# ppc_extbus.net
KiCad netlist of a schematic drawn in Altium Designer
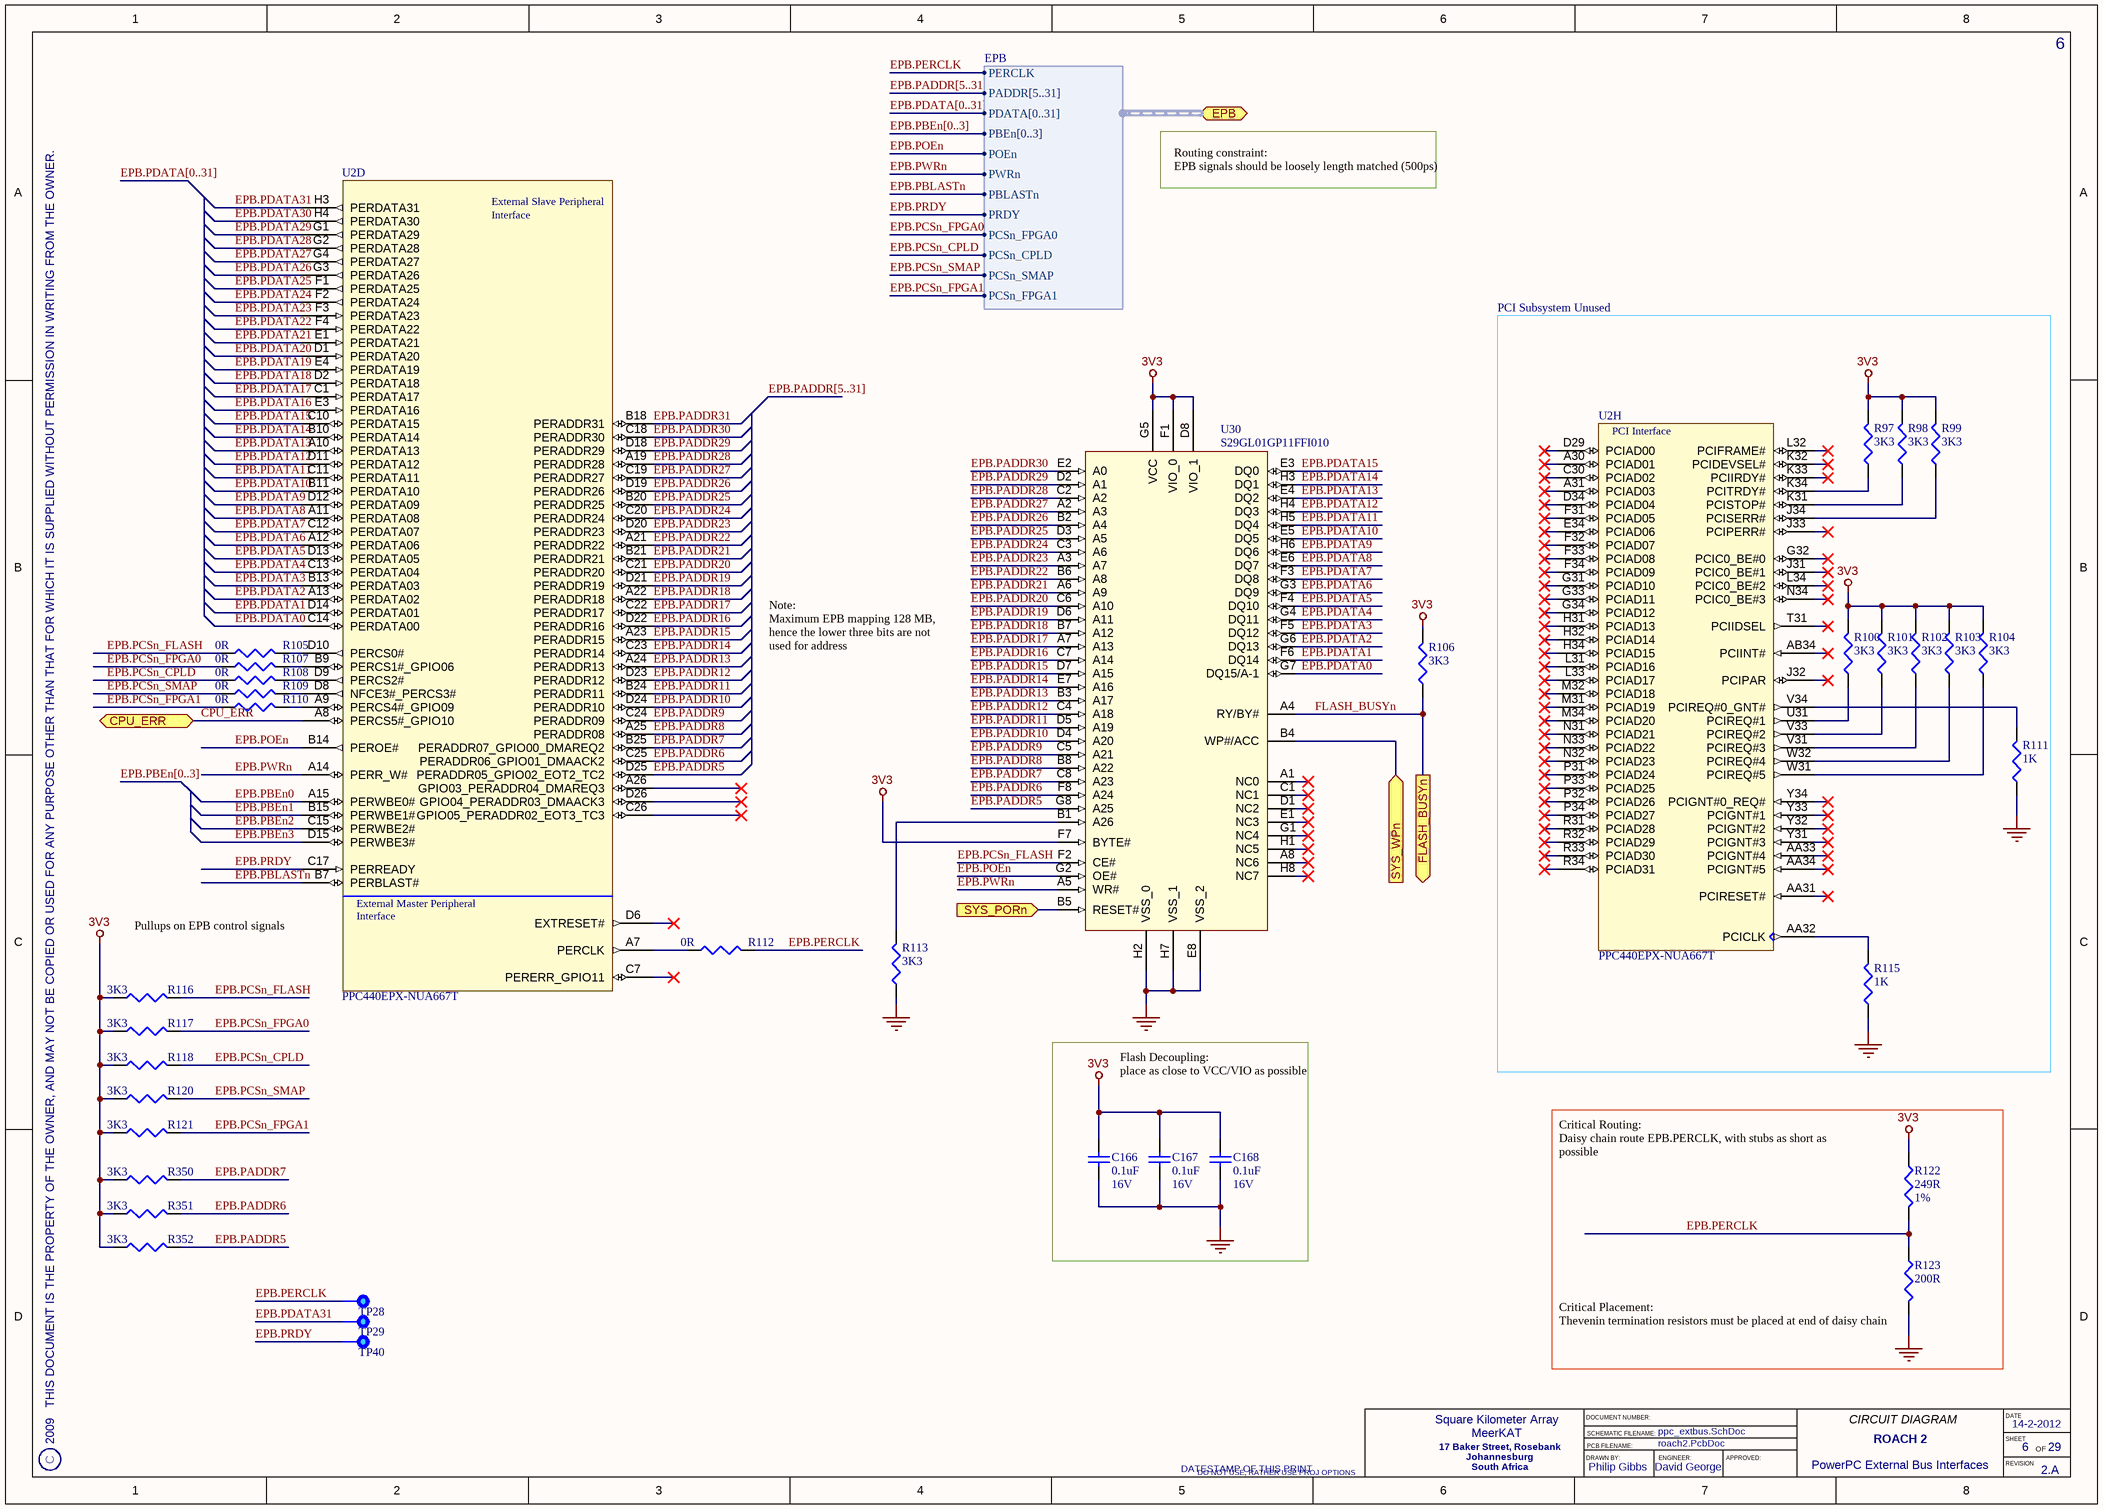
[diagram p0: ppc_extbus.SchDoc]

(export (version "E")
  (design (tool "Eeschema 10.0.6"))
  (components
    (comp (ref "C166")
      (value "0.1uF")
      (footprint "CAPC1005X60L")
      (description "0.1uF, Ceramic Capacitor")
      (fields
        (field (name "MANUFACTURER") "VENKEL")
        (field (name "PARTNUM") "C0402X7R160-104KN")
        (field (name "RATING") "16V")
      )
      (libsource (lib "altium_db") (part "CapStd"))
    )
    (comp (ref "C167")
      (value "0.1uF")
      (footprint "CAPC1005X60L")
      (description "0.1uF, Ceramic Capacitor")
      (fields
        (field (name "MANUFACTURER") "VENKEL")
        (field (name "PARTNUM") "C0402X7R160-104KN")
        (field (name "RATING") "16V")
      )
      (libsource (lib "altium_db") (part "CapStd"))
    )
    (comp (ref "C168")
      (value "0.1uF")
      (footprint "CAPC1005X60L")
      (description "0.1uF, Ceramic Capacitor")
      (fields
        (field (name "MANUFACTURER") "VENKEL")
        (field (name "PARTNUM") "C0402X7R160-104KN")
        (field (name "RATING") "16V")
      )
      (libsource (lib "altium_db") (part "CapStd"))
    )
    (comp (ref "R97")
      (value "3K3")
      (footprint "RESC1005X40L")
      (description "3K3, 1.1mm x 0.5mm, Thick Film Resistor")
      (fields (field (name "MANUFACTURER") "ROYALOHM") (field (name "PARTNUM") "0402WGJ0332T1E"))
      (libsource (lib "altium_db") (part "ResStd"))
    )
    (comp (ref "R98")
      (value "3K3")
      (footprint "RESC1005X40L")
      (description "3K3, 1.1mm x 0.5mm, Thick Film Resistor")
      (fields (field (name "MANUFACTURER") "ROYALOHM") (field (name "PARTNUM") "0402WGJ0332T1E"))
      (libsource (lib "altium_db") (part "ResStd"))
    )
    (comp (ref "R99")
      (value "3K3")
      (footprint "RESC1005X40L")
      (description "3K3, 1.1mm x 0.5mm, Thick Film Resistor")
      (fields (field (name "MANUFACTURER") "ROYALOHM") (field (name "PARTNUM") "0402WGJ0332T1E"))
      (libsource (lib "altium_db") (part "ResStd"))
    )
    (comp (ref "R100")
      (value "3K3")
      (footprint "RESC1005X40L")
      (description "3K3, 1.1mm x 0.5mm, Thick Film Resistor")
      (fields (field (name "MANUFACTURER") "ROYALOHM") (field (name "PARTNUM") "0402WGJ0332T1E"))
      (libsource (lib "altium_db") (part "ResStd"))
    )
    (comp (ref "R101")
      (value "3K3")
      (footprint "RESC1005X40L")
      (description "3K3, 1.1mm x 0.5mm, Thick Film Resistor")
      (fields (field (name "MANUFACTURER") "ROYALOHM") (field (name "PARTNUM") "0402WGJ0332T1E"))
      (libsource (lib "altium_db") (part "ResStd"))
    )
    (comp (ref "R102")
      (value "3K3")
      (footprint "RESC1005X40L")
      (description "3K3, 1.1mm x 0.5mm, Thick Film Resistor")
      (fields (field (name "MANUFACTURER") "ROYALOHM") (field (name "PARTNUM") "0402WGJ0332T1E"))
      (libsource (lib "altium_db") (part "ResStd"))
    )
    (comp (ref "R103")
      (value "3K3")
      (footprint "RESC1005X40L")
      (description "3K3, 1.1mm x 0.5mm, Thick Film Resistor")
      (fields (field (name "MANUFACTURER") "ROYALOHM") (field (name "PARTNUM") "0402WGJ0332T1E"))
      (libsource (lib "altium_db") (part "ResStd"))
    )
    (comp (ref "R104")
      (value "3K3")
      (footprint "RESC1005X40L")
      (description "3K3, 1.1mm x 0.5mm, Thick Film Resistor")
      (fields (field (name "MANUFACTURER") "ROYALOHM") (field (name "PARTNUM") "0402WGJ0332T1E"))
      (libsource (lib "altium_db") (part "ResStd"))
    )
    (comp (ref "R105")
      (value "0R")
      (footprint "RESC1005X40L")
      (description "0R, 1.1mm x 0.5mm, Thick Film Resistor")
      (fields (field (name "MANUFACTURER") "ROYALOHM") (field (name "PARTNUM") "0402WG00000T1E"))
      (libsource (lib "altium_db") (part "ResStd"))
    )
    (comp (ref "R106")
      (value "3K3")
      (footprint "RESC1005X40L")
      (description "3K3, 1.1mm x 0.5mm, Thick Film Resistor")
      (fields (field (name "MANUFACTURER") "ROYALOHM") (field (name "PARTNUM") "0402WGJ0332T1E"))
      (libsource (lib "altium_db") (part "ResStd"))
    )
    (comp (ref "R107")
      (value "0R")
      (footprint "RESC1005X40L")
      (description "0R, 1.1mm x 0.5mm, Thick Film Resistor")
      (fields (field (name "MANUFACTURER") "ROYALOHM") (field (name "PARTNUM") "0402WG00000T1E"))
      (libsource (lib "altium_db") (part "ResStd"))
    )
    (comp (ref "R108")
      (value "0R")
      (footprint "RESC1005X40L")
      (description "0R, 1.1mm x 0.5mm, Thick Film Resistor")
      (fields (field (name "MANUFACTURER") "ROYALOHM") (field (name "PARTNUM") "0402WG00000T1E"))
      (libsource (lib "altium_db") (part "ResStd"))
    )
    (comp (ref "R109")
      (value "0R")
      (footprint "RESC1005X40L")
      (description "0R, 1.1mm x 0.5mm, Thick Film Resistor")
      (fields (field (name "MANUFACTURER") "ROYALOHM") (field (name "PARTNUM") "0402WG00000T1E"))
      (libsource (lib "altium_db") (part "ResStd"))
    )
    (comp (ref "R110")
      (value "0R")
      (footprint "RESC1005X40L")
      (description "0R, 1.1mm x 0.5mm, Thick Film Resistor")
      (fields (field (name "MANUFACTURER") "ROYALOHM") (field (name "PARTNUM") "0402WG00000T1E"))
      (libsource (lib "altium_db") (part "ResStd"))
    )
    (comp (ref "R111")
      (value "1K")
      (footprint "RESC1005X40L")
      (description "1K, 1.1mm x 0.5mm, Thick Film Resistor")
      (fields (field (name "MANUFACTURER") "ROYALOHM") (field (name "PARTNUM") "0402WGJ0102T1E"))
      (libsource (lib "altium_db") (part "ResStd"))
    )
    (comp (ref "R112")
      (value "0R")
      (footprint "RESC1005X40L")
      (description "0R, 1.1mm x 0.5mm, Thick Film Resistor")
      (fields (field (name "MANUFACTURER") "ROYALOHM") (field (name "PARTNUM") "0402WG00000T1E"))
      (libsource (lib "altium_db") (part "ResStd"))
    )
    (comp (ref "R113")
      (value "3K3")
      (footprint "RESC1005X40L")
      (description "3K3, 1.1mm x 0.5mm, Thick Film Resistor")
      (fields (field (name "MANUFACTURER") "ROYALOHM") (field (name "PARTNUM") "0402WGJ0332T1E"))
      (libsource (lib "altium_db") (part "ResStd"))
    )
    (comp (ref "R115")
      (value "1K")
      (footprint "RESC1005X40L")
      (description "1K, 1.1mm x 0.5mm, Thick Film Resistor")
      (fields (field (name "MANUFACTURER") "ROYALOHM") (field (name "PARTNUM") "0402WGJ0102T1E"))
      (libsource (lib "altium_db") (part "ResStd"))
    )
    (comp (ref "R116")
      (value "3K3")
      (footprint "RESC1005X40L")
      (description "3K3, 1.1mm x 0.5mm, Thick Film Resistor")
      (fields (field (name "MANUFACTURER") "ROYALOHM") (field (name "PARTNUM") "0402WGJ0332T1E"))
      (libsource (lib "altium_db") (part "ResStd"))
    )
    (comp (ref "R117")
      (value "3K3")
      (footprint "RESC1005X40L")
      (description "3K3, 1.1mm x 0.5mm, Thick Film Resistor")
      (fields (field (name "MANUFACTURER") "ROYALOHM") (field (name "PARTNUM") "0402WGJ0332T1E"))
      (libsource (lib "altium_db") (part "ResStd"))
    )
    (comp (ref "R118")
      (value "3K3")
      (footprint "RESC1005X40L")
      (description "3K3, 1.1mm x 0.5mm, Thick Film Resistor")
      (fields (field (name "MANUFACTURER") "ROYALOHM") (field (name "PARTNUM") "0402WGJ0332T1E"))
      (libsource (lib "altium_db") (part "ResStd"))
    )
    (comp (ref "R120")
      (value "3K3")
      (footprint "RESC1005X40L")
      (description "3K3, 1.1mm x 0.5mm, Thick Film Resistor")
      (fields (field (name "MANUFACTURER") "ROYALOHM") (field (name "PARTNUM") "0402WGJ0332T1E"))
      (libsource (lib "altium_db") (part "ResStd"))
    )
    (comp (ref "R121")
      (value "3K3")
      (footprint "RESC1005X40L")
      (description "3K3, 1.1mm x 0.5mm, Thick Film Resistor")
      (fields (field (name "MANUFACTURER") "ROYALOHM") (field (name "PARTNUM") "0402WGJ0332T1E"))
      (libsource (lib "altium_db") (part "ResStd"))
    )
    (comp (ref "R122")
      (value "249R")
      (footprint "RESC1005X40L")
      (description "249R, 1.1mm x 0.5mm, Thick Film Resistor")
      (fields
        (field (name "MANUFACTURER") "ROYALOHM")
        (field (name "PARTNUM") "0402WGF2490T1E")
        (field (name "TOLERANCE") "1%")
      )
      (libsource (lib "altium_db") (part "ResStd"))
    )
    (comp (ref "R123")
      (value "200R")
      (footprint "RESC1005X40L")
      (description "200R, 1.1mm x 0.5mm, Thick Film Resistor")
      (fields (field (name "MANUFACTURER") "ROYALOHM") (field (name "PARTNUM") "0402WGF0201T1E"))
      (libsource (lib "altium_db") (part "ResStd"))
    )
    (comp (ref "R350")
      (value "3K3")
      (footprint "RESC1005X40L")
      (description "3K3, 1.1mm x 0.5mm, Thick Film Resistor")
      (fields (field (name "MANUFACTURER") "ROYALOHM") (field (name "PARTNUM") "0402WGJ0332T1E"))
      (libsource (lib "altium_db") (part "ResStd"))
    )
    (comp (ref "R351")
      (value "3K3")
      (footprint "RESC1005X40L")
      (description "3K3, 1.1mm x 0.5mm, Thick Film Resistor")
      (fields (field (name "MANUFACTURER") "ROYALOHM") (field (name "PARTNUM") "0402WGJ0332T1E"))
      (libsource (lib "altium_db") (part "ResStd"))
    )
    (comp (ref "R352")
      (value "3K3")
      (footprint "RESC1005X40L")
      (description "3K3, 1.1mm x 0.5mm, Thick Film Resistor")
      (fields (field (name "MANUFACTURER") "ROYALOHM") (field (name "PARTNUM") "0402WGJ0332T1E"))
      (libsource (lib "altium_db") (part "ResStd"))
    )
    (comp (ref "TP28")
      (value "Testpoint")
      (footprint "TP100")
      (description "1mm Diameter, through-hole, Circular Test-point")
      (libsource (lib "altium_db") (part "Testpoint"))
    )
    (comp (ref "TP29")
      (value "Testpoint")
      (footprint "TP100")
      (description "1mm Diameter, through-hole, Circular Test-point")
      (libsource (lib "altium_db") (part "Testpoint"))
    )
    (comp (ref "TP40")
      (value "Testpoint")
      (footprint "TP100")
      (description "1mm Diameter, through-hole, Circular Test-point")
      (libsource (lib "altium_db") (part "Testpoint"))
    )
    (comp (ref "U2")
      (value "PPC440EPX-NUA667T")
      (footprint "TE-PBGA680")
      (description "667MHz, non-RoHS, PPC440EPx uProcessor")
      (fields (field (name "MANUFACTURER") "Applied Micro"))
      (libsource (lib "altium_db") (part "PPC440EPX"))
    )
    (comp (ref "U30")
      (value "S29GL01GP11FFI010")
      (footprint "LAA064")
      (description "3V, 1 Gigabit NOR Flash")
      (fields (field (name "MANUFACTURER") "Spansion"))
      (libsource (lib "altium_db") (part "S29GL01GP"))
    )
  )
  (nets
    (net (code "2") (name "/CPU_ERR") (class "Default")
      (node (ref "U2") (pin "A8") (pinfunction "PERCS5#_GPIO10_A8") (pintype "bidirectional"))
    )
    (net (code "3") (name "/EPB.PADDR5") (class "Default")
      (node (ref "R352") (pin "2") (pinfunction "2_2") (pintype "passive"))
      (node (ref "U2") (pin "D25") (pinfunction "PERADDR05_GPIO02_EOT2_TC2_D25") (pintype "bidirectional"))
      (node (ref "U30") (pin "G8") (pinfunction "A25_G8") (pintype "input"))
    )
    (net (code "4") (name "/EPB.PADDR6") (class "Default")
      (node (ref "R351") (pin "2") (pinfunction "2_2") (pintype "passive"))
      (node (ref "U2") (pin "C25") (pinfunction "PERADDR06_GPIO01_DMAACK2_C25") (pintype "bidirectional"))
      (node (ref "U30") (pin "F8") (pinfunction "A24_F8") (pintype "input"))
    )
    (net (code "5") (name "/EPB.PADDR7") (class "Default")
      (node (ref "R350") (pin "2") (pinfunction "2_2") (pintype "passive"))
      (node (ref "U2") (pin "B25") (pinfunction "PERADDR07_GPIO00_DMAREQ2_B25") (pintype "bidirectional"))
      (node (ref "U30") (pin "C8") (pinfunction "A23_C8") (pintype "input"))
    )
    (net (code "6") (name "/EPB.PADDR8") (class "Default")
      (node (ref "U2") (pin "A25") (pinfunction "PERADDR08_A25") (pintype "bidirectional"))
      (node (ref "U30") (pin "B8") (pinfunction "A22_B8") (pintype "input"))
    )
    (net (code "7") (name "/EPB.PADDR9") (class "Default")
      (node (ref "U2") (pin "C24") (pinfunction "PERADDR09_C24") (pintype "bidirectional"))
      (node (ref "U30") (pin "C5") (pinfunction "A21_C5") (pintype "input"))
    )
    (net (code "8") (name "/EPB.PADDR10") (class "Default")
      (node (ref "U2") (pin "D24") (pinfunction "PERADDR10_D24") (pintype "bidirectional"))
      (node (ref "U30") (pin "D4") (pinfunction "A20_D4") (pintype "input"))
    )
    (net (code "9") (name "/EPB.PADDR11") (class "Default")
      (node (ref "U2") (pin "B24") (pinfunction "PERADDR11_B24") (pintype "bidirectional"))
      (node (ref "U30") (pin "D5") (pinfunction "A19_D5") (pintype "input"))
    )
    (net (code "10") (name "/EPB.PADDR12") (class "Default")
      (node (ref "U2") (pin "D23") (pinfunction "PERADDR12_D23") (pintype "bidirectional"))
      (node (ref "U30") (pin "C4") (pinfunction "A18_C4") (pintype "input"))
    )
    (net (code "11") (name "/EPB.PADDR13") (class "Default")
      (node (ref "U2") (pin "A24") (pinfunction "PERADDR13_A24") (pintype "bidirectional"))
      (node (ref "U30") (pin "B3") (pinfunction "A17_B3") (pintype "input"))
    )
    (net (code "12") (name "/EPB.PADDR14") (class "Default")
      (node (ref "U2") (pin "C23") (pinfunction "PERADDR14_C23") (pintype "bidirectional"))
      (node (ref "U30") (pin "E7") (pinfunction "A16_E7") (pintype "input"))
    )
    (net (code "13") (name "/EPB.PADDR15") (class "Default")
      (node (ref "U2") (pin "A23") (pinfunction "PERADDR15_A23") (pintype "bidirectional"))
      (node (ref "U30") (pin "D7") (pinfunction "A15_D7") (pintype "input"))
    )
    (net (code "14") (name "/EPB.PADDR16") (class "Default")
      (node (ref "U2") (pin "D22") (pinfunction "PERADDR16_D22") (pintype "bidirectional"))
      (node (ref "U30") (pin "C7") (pinfunction "A14_C7") (pintype "input"))
    )
    (net (code "15") (name "/EPB.PADDR17") (class "Default")
      (node (ref "U2") (pin "C22") (pinfunction "PERADDR17_C22") (pintype "bidirectional"))
      (node (ref "U30") (pin "A7") (pinfunction "A13_A7") (pintype "input"))
    )
    (net (code "16") (name "/EPB.PADDR18") (class "Default")
      (node (ref "U2") (pin "A22") (pinfunction "PERADDR18_A22") (pintype "bidirectional"))
      (node (ref "U30") (pin "B7") (pinfunction "A12_B7") (pintype "input"))
    )
    (net (code "17") (name "/EPB.PADDR19") (class "Default")
      (node (ref "U2") (pin "D21") (pinfunction "PERADDR19_D21") (pintype "bidirectional"))
      (node (ref "U30") (pin "D6") (pinfunction "A11_D6") (pintype "input"))
    )
    (net (code "18") (name "/EPB.PADDR20") (class "Default")
      (node (ref "U2") (pin "C21") (pinfunction "PERADDR20_C21") (pintype "bidirectional"))
      (node (ref "U30") (pin "C6") (pinfunction "A10_C6") (pintype "input"))
    )
    (net (code "19") (name "/EPB.PADDR21") (class "Default")
      (node (ref "U2") (pin "B21") (pinfunction "PERADDR21_B21") (pintype "bidirectional"))
      (node (ref "U30") (pin "A6") (pinfunction "A9_A6") (pintype "input"))
    )
    (net (code "20") (name "/EPB.PADDR22") (class "Default")
      (node (ref "U2") (pin "A21") (pinfunction "PERADDR22_A21") (pintype "bidirectional"))
      (node (ref "U30") (pin "B6") (pinfunction "A8_B6") (pintype "input"))
    )
    (net (code "21") (name "/EPB.PADDR23") (class "Default")
      (node (ref "U2") (pin "D20") (pinfunction "PERADDR23_D20") (pintype "bidirectional"))
      (node (ref "U30") (pin "A3") (pinfunction "A7_A3") (pintype "input"))
    )
    (net (code "22") (name "/EPB.PADDR24") (class "Default")
      (node (ref "U2") (pin "C20") (pinfunction "PERADDR24_C20") (pintype "bidirectional"))
      (node (ref "U30") (pin "C3") (pinfunction "A6_C3") (pintype "input"))
    )
    (net (code "23") (name "/EPB.PADDR25") (class "Default")
      (node (ref "U2") (pin "B20") (pinfunction "PERADDR25_B20") (pintype "bidirectional"))
      (node (ref "U30") (pin "D3") (pinfunction "A5_D3") (pintype "input"))
    )
    (net (code "24") (name "/EPB.PADDR26") (class "Default")
      (node (ref "U2") (pin "D19") (pinfunction "PERADDR26_D19") (pintype "bidirectional"))
      (node (ref "U30") (pin "B2") (pinfunction "A4_B2") (pintype "input"))
    )
    (net (code "25") (name "/EPB.PADDR27") (class "Default")
      (node (ref "U2") (pin "C19") (pinfunction "PERADDR27_C19") (pintype "bidirectional"))
      (node (ref "U30") (pin "A2") (pinfunction "A3_A2") (pintype "input"))
    )
    (net (code "26") (name "/EPB.PADDR28") (class "Default")
      (node (ref "U2") (pin "A19") (pinfunction "PERADDR28_A19") (pintype "bidirectional"))
      (node (ref "U30") (pin "C2") (pinfunction "A2_C2") (pintype "input"))
    )
    (net (code "27") (name "/EPB.PADDR29") (class "Default")
      (node (ref "U2") (pin "D18") (pinfunction "PERADDR29_D18") (pintype "bidirectional"))
      (node (ref "U30") (pin "D2") (pinfunction "A1_D2") (pintype "input"))
    )
    (net (code "28") (name "/EPB.PADDR30") (class "Default")
      (node (ref "U2") (pin "C18") (pinfunction "PERADDR30_C18") (pintype "bidirectional"))
      (node (ref "U30") (pin "E2") (pinfunction "A0_E2") (pintype "input"))
    )
    (net (code "29") (name "/EPB.PADDR31") (class "Default")
      (node (ref "U2") (pin "B18") (pinfunction "PERADDR31_B18") (pintype "bidirectional"))
    )
    (net (code "31") (name "/EPB.PBEn0") (class "Default")
      (node (ref "U2") (pin "A15") (pinfunction "PERWBE0#_A15") (pintype "bidirectional"))
    )
    (net (code "32") (name "/EPB.PBEn1") (class "Default")
      (node (ref "U2") (pin "B15") (pinfunction "PERWBE1#_B15") (pintype "bidirectional"))
    )
    (net (code "33") (name "/EPB.PBEn2") (class "Default")
      (node (ref "U2") (pin "C15") (pinfunction "PERWBE2#_C15") (pintype "bidirectional"))
    )
    (net (code "34") (name "/EPB.PBEn3") (class "Default")
      (node (ref "U2") (pin "D15") (pinfunction "PERWBE3#_D15") (pintype "bidirectional"))
    )
    (net (code "36") (name "/EPB.PBLASTn") (class "Default")
      (node (ref "U2") (pin "B7") (pinfunction "PERBLAST#_B7") (pintype "bidirectional"))
    )
    (net (code "37") (name "/EPB.PCSn_CPLD") (class "Default")
      (node (ref "R108") (pin "1") (pinfunction "1_1") (pintype "passive"))
      (node (ref "R118") (pin "2") (pinfunction "2_2") (pintype "passive"))
    )
    (net (code "38") (name "/EPB.PCSn_FLASH") (class "Default")
      (node (ref "R105") (pin "1") (pinfunction "1_1") (pintype "passive"))
      (node (ref "R116") (pin "2") (pinfunction "2_2") (pintype "passive"))
      (node (ref "U30") (pin "F2") (pinfunction "CE#_F2") (pintype "input"))
    )
    (net (code "39") (name "/EPB.PCSn_FPGA0") (class "Default")
      (node (ref "R107") (pin "1") (pinfunction "1_1") (pintype "passive"))
      (node (ref "R117") (pin "2") (pinfunction "2_2") (pintype "passive"))
    )
    (net (code "40") (name "/EPB.PCSn_FPGA1") (class "Default")
      (node (ref "R110") (pin "1") (pinfunction "1_1") (pintype "passive"))
      (node (ref "R121") (pin "2") (pinfunction "2_2") (pintype "passive"))
    )
    (net (code "41") (name "/EPB.PCSn_SMAP") (class "Default")
      (node (ref "R109") (pin "1") (pinfunction "1_1") (pintype "passive"))
      (node (ref "R120") (pin "2") (pinfunction "2_2") (pintype "passive"))
    )
    (net (code "42") (name "/EPB.PDATA0") (class "Default")
      (node (ref "U2") (pin "C14") (pinfunction "PERDATA00_C14") (pintype "bidirectional"))
      (node (ref "U30") (pin "G7") (pinfunction "DQ15/A-1_G7") (pintype "bidirectional"))
    )
    (net (code "43") (name "/EPB.PDATA1") (class "Default")
      (node (ref "U2") (pin "D14") (pinfunction "PERDATA01_D14") (pintype "bidirectional"))
      (node (ref "U30") (pin "F6") (pinfunction "DQ14_F6") (pintype "bidirectional"))
    )
    (net (code "44") (name "/EPB.PDATA2") (class "Default")
      (node (ref "U2") (pin "A13") (pinfunction "PERDATA02_A13") (pintype "bidirectional"))
      (node (ref "U30") (pin "G6") (pinfunction "DQ13_G6") (pintype "bidirectional"))
    )
    (net (code "45") (name "/EPB.PDATA3") (class "Default")
      (node (ref "U2") (pin "B13") (pinfunction "PERDATA03_B13") (pintype "bidirectional"))
      (node (ref "U30") (pin "F5") (pinfunction "DQ12_F5") (pintype "bidirectional"))
    )
    (net (code "46") (name "/EPB.PDATA4") (class "Default")
      (node (ref "U2") (pin "C13") (pinfunction "PERDATA04_C13") (pintype "bidirectional"))
      (node (ref "U30") (pin "G4") (pinfunction "DQ11_G4") (pintype "bidirectional"))
    )
    (net (code "47") (name "/EPB.PDATA5") (class "Default")
      (node (ref "U2") (pin "D13") (pinfunction "PERDATA05_D13") (pintype "bidirectional"))
      (node (ref "U30") (pin "F4") (pinfunction "DQ10_F4") (pintype "bidirectional"))
    )
    (net (code "48") (name "/EPB.PDATA6") (class "Default")
      (node (ref "U2") (pin "A12") (pinfunction "PERDATA06_A12") (pintype "bidirectional"))
      (node (ref "U30") (pin "G3") (pinfunction "DQ9_G3") (pintype "bidirectional"))
    )
    (net (code "49") (name "/EPB.PDATA7") (class "Default")
      (node (ref "U2") (pin "C12") (pinfunction "PERDATA07_C12") (pintype "bidirectional"))
      (node (ref "U30") (pin "F3") (pinfunction "DQ8_F3") (pintype "bidirectional"))
    )
    (net (code "50") (name "/EPB.PDATA8") (class "Default")
      (node (ref "U2") (pin "A11") (pinfunction "PERDATA08_A11") (pintype "bidirectional"))
      (node (ref "U30") (pin "E6") (pinfunction "DQ7_E6") (pintype "bidirectional"))
    )
    (net (code "51") (name "/EPB.PDATA9") (class "Default")
      (node (ref "U2") (pin "D12") (pinfunction "PERDATA09_D12") (pintype "bidirectional"))
      (node (ref "U30") (pin "H6") (pinfunction "DQ6_H6") (pintype "bidirectional"))
    )
    (net (code "52") (name "/EPB.PDATA10") (class "Default")
      (node (ref "U2") (pin "B11") (pinfunction "PERDATA10_B11") (pintype "bidirectional"))
      (node (ref "U30") (pin "E5") (pinfunction "DQ5_E5") (pintype "bidirectional"))
    )
    (net (code "53") (name "/EPB.PDATA11") (class "Default")
      (node (ref "U2") (pin "C11") (pinfunction "PERDATA11_C11") (pintype "bidirectional"))
      (node (ref "U30") (pin "H5") (pinfunction "DQ4_H5") (pintype "bidirectional"))
    )
    (net (code "54") (name "/EPB.PDATA12") (class "Default")
      (node (ref "U2") (pin "D11") (pinfunction "PERDATA12_D11") (pintype "bidirectional"))
      (node (ref "U30") (pin "H4") (pinfunction "DQ3_H4") (pintype "bidirectional"))
    )
    (net (code "55") (name "/EPB.PDATA13") (class "Default")
      (node (ref "U2") (pin "A10") (pinfunction "PERDATA13_A10") (pintype "bidirectional"))
      (node (ref "U30") (pin "E4") (pinfunction "DQ2_E4") (pintype "bidirectional"))
    )
    (net (code "56") (name "/EPB.PDATA14") (class "Default")
      (node (ref "U2") (pin "B10") (pinfunction "PERDATA14_B10") (pintype "bidirectional"))
      (node (ref "U30") (pin "H3") (pinfunction "DQ1_H3") (pintype "bidirectional"))
    )
    (net (code "57") (name "/EPB.PDATA15") (class "Default")
      (node (ref "U2") (pin "C10") (pinfunction "PERDATA15_C10") (pintype "bidirectional"))
      (node (ref "U30") (pin "E3") (pinfunction "DQ0_E3") (pintype "bidirectional"))
    )
    (net (code "58") (name "/EPB.PDATA16") (class "Default")
      (node (ref "U2") (pin "E3") (pinfunction "PERDATA16_E3") (pintype "input"))
    )
    (net (code "59") (name "/EPB.PDATA17") (class "Default")
      (node (ref "U2") (pin "C1") (pinfunction "PERDATA17_C1") (pintype "input"))
    )
    (net (code "60") (name "/EPB.PDATA18") (class "Default")
      (node (ref "U2") (pin "D2") (pinfunction "PERDATA18_D2") (pintype "input"))
    )
    (net (code "61") (name "/EPB.PDATA19") (class "Default")
      (node (ref "U2") (pin "E4") (pinfunction "PERDATA19_E4") (pintype "input"))
    )
    (net (code "62") (name "/EPB.PDATA20") (class "Default")
      (node (ref "U2") (pin "D1") (pinfunction "PERDATA20_D1") (pintype "input"))
    )
    (net (code "63") (name "/EPB.PDATA21") (class "Default")
      (node (ref "U2") (pin "E1") (pinfunction "PERDATA21_E1") (pintype "input"))
    )
    (net (code "64") (name "/EPB.PDATA22") (class "Default")
      (node (ref "U2") (pin "F4") (pinfunction "PERDATA22_F4") (pintype "input"))
    )
    (net (code "65") (name "/EPB.PDATA23") (class "Default")
      (node (ref "U2") (pin "F3") (pinfunction "PERDATA23_F3") (pintype "input"))
    )
    (net (code "66") (name "/EPB.PDATA24") (class "Default")
      (node (ref "U2") (pin "F2") (pinfunction "PERDATA24_F2") (pintype "output"))
    )
    (net (code "67") (name "/EPB.PDATA25") (class "Default")
      (node (ref "U2") (pin "F1") (pinfunction "PERDATA25_F1") (pintype "output"))
    )
    (net (code "68") (name "/EPB.PDATA26") (class "Default")
      (node (ref "U2") (pin "G3") (pinfunction "PERDATA26_G3") (pintype "output"))
    )
    (net (code "69") (name "/EPB.PDATA27") (class "Default")
      (node (ref "U2") (pin "G4") (pinfunction "PERDATA27_G4") (pintype "output"))
    )
    (net (code "70") (name "/EPB.PDATA28") (class "Default")
      (node (ref "U2") (pin "G2") (pinfunction "PERDATA28_G2") (pintype "output"))
    )
    (net (code "71") (name "/EPB.PDATA29") (class "Default")
      (node (ref "U2") (pin "G1") (pinfunction "PERDATA29_G1") (pintype "output"))
    )
    (net (code "72") (name "/EPB.PDATA30") (class "Default")
      (node (ref "U2") (pin "H4") (pinfunction "PERDATA30_H4") (pintype "output"))
    )
    (net (code "73") (name "/EPB.PDATA31") (class "Default")
      (node (ref "TP29") (pin "1") (pinfunction "1_1") (pintype "passive"))
      (node (ref "U2") (pin "H3") (pinfunction "PERDATA31_H3") (pintype "output"))
    )
    (net (code "75") (name "/EPB.PERCLK") (class "Default")
      (node (ref "R112") (pin "2") (pinfunction "2_2") (pintype "passive"))
      (node (ref "R122") (pin "2") (pinfunction "2_2") (pintype "passive"))
      (node (ref "R123") (pin "1") (pinfunction "1_1") (pintype "passive"))
      (node (ref "TP28") (pin "1") (pinfunction "1_1") (pintype "passive"))
    )
    (net (code "76") (name "/EPB.POEn") (class "Default")
      (node (ref "U2") (pin "B14") (pinfunction "PEROE#_B14") (pintype "output"))
      (node (ref "U30") (pin "G2") (pinfunction "OE#_G2") (pintype "input"))
    )
    (net (code "77") (name "/EPB.PRDY") (class "Default")
      (node (ref "TP40") (pin "1") (pinfunction "1_1") (pintype "passive"))
      (node (ref "U2") (pin "C17") (pinfunction "PERREADY_C17") (pintype "input"))
    )
    (net (code "78") (name "/EPB.PWRn") (class "Default")
      (node (ref "U2") (pin "A14") (pinfunction "PERR_W#_A14") (pintype "bidirectional"))
      (node (ref "U30") (pin "A5") (pinfunction "WR#_A5") (pintype "input"))
    )
    (net (code "80") (name "/FLASH_BUSYn") (class "Default")
      (node (ref "R106") (pin "1") (pinfunction "1_1") (pintype "passive"))
      (node (ref "U30") (pin "A4") (pinfunction "RY/BY#_A4") (pintype "open_collector"))
    )
    (net (code "81") (name "/SYS_PORn") (class "Default")
      (node (ref "U30") (pin "B5") (pinfunction "RESET#_B5") (pintype "input"))
    )
    (net (code "82") (name "/SYS_WPn") (class "Default")
      (node (ref "U30") (pin "B4") (pinfunction "WP#/ACC_B4") (pintype "open_collector"))
    )
    (net (code "84") (name "3V3") (class "Default")
      (node (ref "C166") (pin "2") (pinfunction "2_2") (pintype "passive"))
      (node (ref "C167") (pin "2") (pinfunction "2_2") (pintype "passive"))
      (node (ref "C168") (pin "2") (pinfunction "2_2") (pintype "passive"))
      (node (ref "R100") (pin "2") (pinfunction "2_2") (pintype "passive"))
      (node (ref "R101") (pin "2") (pinfunction "2_2") (pintype "passive"))
      (node (ref "R102") (pin "2") (pinfunction "2_2") (pintype "passive"))
      (node (ref "R103") (pin "2") (pinfunction "2_2") (pintype "passive"))
      (node (ref "R104") (pin "2") (pinfunction "2_2") (pintype "passive"))
      (node (ref "R106") (pin "2") (pinfunction "2_2") (pintype "passive"))
      (node (ref "R116") (pin "1") (pinfunction "1_1") (pintype "passive"))
      (node (ref "R117") (pin "1") (pinfunction "1_1") (pintype "passive"))
      (node (ref "R118") (pin "1") (pinfunction "1_1") (pintype "passive"))
      (node (ref "R120") (pin "1") (pinfunction "1_1") (pintype "passive"))
      (node (ref "R121") (pin "1") (pinfunction "1_1") (pintype "passive"))
      (node (ref "R122") (pin "1") (pinfunction "1_1") (pintype "passive"))
      (node (ref "R350") (pin "1") (pinfunction "1_1") (pintype "passive"))
      (node (ref "R351") (pin "1") (pinfunction "1_1") (pintype "passive"))
      (node (ref "R352") (pin "1") (pinfunction "1_1") (pintype "passive"))
      (node (ref "R97") (pin "2") (pinfunction "2_2") (pintype "passive"))
      (node (ref "R98") (pin "2") (pinfunction "2_2") (pintype "passive"))
      (node (ref "R99") (pin "2") (pinfunction "2_2") (pintype "passive"))
      (node (ref "U30") (pin "D8") (pinfunction "VIO_1_D8") (pintype "passive"))
      (node (ref "U30") (pin "F1") (pinfunction "VIO_0_F1") (pintype "passive"))
      (node (ref "U30") (pin "F7") (pinfunction "BYTE#_F7") (pintype "input"))
      (node (ref "U30") (pin "G5") (pinfunction "VCC_G5") (pintype "passive"))
    )
    (net (code "85") (name "GND") (class "Default")
      (node (ref "C166") (pin "1") (pinfunction "1_1") (pintype "passive"))
      (node (ref "C167") (pin "1") (pinfunction "1_1") (pintype "passive"))
      (node (ref "C168") (pin "1") (pinfunction "1_1") (pintype "passive"))
      (node (ref "R111") (pin "1") (pinfunction "1_1") (pintype "passive"))
      (node (ref "R113") (pin "1") (pinfunction "1_1") (pintype "passive"))
      (node (ref "R115") (pin "1") (pinfunction "1_1") (pintype "passive"))
      (node (ref "R123") (pin "2") (pinfunction "2_2") (pintype "passive"))
      (node (ref "U30") (pin "E8") (pinfunction "VSS_2_E8") (pintype "passive"))
      (node (ref "U30") (pin "H2") (pinfunction "VSS_0_H2") (pintype "passive"))
      (node (ref "U30") (pin "H7") (pinfunction "VSS_1_H7") (pintype "passive"))
    )
    (net (code "86") (name "Net-(U2D-NFCE3#_PERCS3#)") (class "Default")
      (node (ref "R109") (pin "2") (pinfunction "2_2") (pintype "passive"))
      (node (ref "U2") (pin "D8") (pinfunction "NFCE3#_PERCS3#_D8") (pintype "output"))
    )
    (net (code "87") (name "Net-(U2D-PERCLK)") (class "Default")
      (node (ref "R112") (pin "1") (pinfunction "1_1") (pintype "passive"))
      (node (ref "U2") (pin "A7") (pinfunction "PERCLK_A7") (pintype "output"))
    )
    (net (code "88") (name "Net-(U2D-PERCS0#)") (class "Default")
      (node (ref "R105") (pin "2") (pinfunction "2_2") (pintype "passive"))
      (node (ref "U2") (pin "D10") (pinfunction "PERCS0#_D10") (pintype "output"))
    )
    (net (code "89") (name "Net-(U2D-PERCS1#_GPIO06)") (class "Default")
      (node (ref "R107") (pin "2") (pinfunction "2_2") (pintype "passive"))
      (node (ref "U2") (pin "B9") (pinfunction "PERCS1#_GPIO06_B9") (pintype "bidirectional"))
    )
    (net (code "90") (name "Net-(U2D-PERCS2#)") (class "Default")
      (node (ref "R108") (pin "2") (pinfunction "2_2") (pintype "passive"))
      (node (ref "U2") (pin "D9") (pinfunction "PERCS2#_D9") (pintype "output"))
    )
    (net (code "91") (name "Net-(U2D-PERCS4#_GPIO09)") (class "Default")
      (node (ref "R110") (pin "2") (pinfunction "2_2") (pintype "passive"))
      (node (ref "U2") (pin "A9") (pinfunction "PERCS4#_GPIO09_A9") (pintype "bidirectional"))
    )
    (net (code "92") (name "Net-(U2H-PCICLK)") (class "Default")
      (node (ref "R115") (pin "2") (pinfunction "2_2") (pintype "passive"))
      (node (ref "U2") (pin "AA32") (pinfunction "PCICLK_AA32") (pintype "output"))
    )
    (net (code "93") (name "Net-(U2H-PCIREQ#0_GNT#)") (class "Default")
      (node (ref "R111") (pin "2") (pinfunction "2_2") (pintype "passive"))
      (node (ref "U2") (pin "V34") (pinfunction "PCIREQ#0_GNT#_V34") (pintype "output"))
    )
    (net (code "94") (name "Net-(U2H-PCIREQ#1)") (class "Default")
      (node (ref "R100") (pin "1") (pinfunction "1_1") (pintype "passive"))
      (node (ref "U2") (pin "U31") (pinfunction "PCIREQ#1_U31") (pintype "output"))
    )
    (net (code "95") (name "Net-(U2H-PCIREQ#2)") (class "Default")
      (node (ref "R101") (pin "1") (pinfunction "1_1") (pintype "passive"))
      (node (ref "U2") (pin "V33") (pinfunction "PCIREQ#2_V33") (pintype "output"))
    )
    (net (code "96") (name "Net-(U2H-PCIREQ#3)") (class "Default")
      (node (ref "R102") (pin "1") (pinfunction "1_1") (pintype "passive"))
      (node (ref "U2") (pin "V31") (pinfunction "PCIREQ#3_V31") (pintype "output"))
    )
    (net (code "97") (name "Net-(U2H-PCIREQ#4)") (class "Default")
      (node (ref "R103") (pin "1") (pinfunction "1_1") (pintype "passive"))
      (node (ref "U2") (pin "W32") (pinfunction "PCIREQ#4_W32") (pintype "output"))
    )
    (net (code "98") (name "Net-(U2H-PCIREQ#5)") (class "Default")
      (node (ref "R104") (pin "1") (pinfunction "1_1") (pintype "passive"))
      (node (ref "U2") (pin "W31") (pinfunction "PCIREQ#5_W31") (pintype "output"))
    )
    (net (code "99") (name "Net-(U2H-PCISERR#)") (class "Default")
      (node (ref "R99") (pin "1") (pinfunction "1_1") (pintype "passive"))
      (node (ref "U2") (pin "J34") (pinfunction "PCISERR#_J34") (pintype "bidirectional"))
    )
    (net (code "100") (name "Net-(U2H-PCISTOP#)") (class "Default")
      (node (ref "R98") (pin "1") (pinfunction "1_1") (pintype "passive"))
      (node (ref "U2") (pin "K31") (pinfunction "PCISTOP#_K31") (pintype "bidirectional"))
    )
    (net (code "101") (name "Net-(U2H-PCITRDY#)") (class "Default")
      (node (ref "R97") (pin "1") (pinfunction "1_1") (pintype "passive"))
      (node (ref "U2") (pin "K34") (pinfunction "PCITRDY#_K34") (pintype "bidirectional"))
    )
    (net (code "102") (name "Net-(U30-A26)") (class "Default")
      (node (ref "R113") (pin "2") (pinfunction "2_2") (pintype "passive"))
      (node (ref "U30") (pin "B1") (pinfunction "A26_B1") (pintype "input"))
    )
    (net (code "103") (name "unconnected-(U2D-EXTRESET#-PadD6)") (class "Default")
      (node (ref "U2") (pin "D6") (pinfunction "EXTRESET#_D6") (pintype "output+no_connect"))
    )
    (net (code "104") (name "unconnected-(U2D-GPIO03_PERADDR04_DMAREQ3-PadA26)") (class "Default")
      (node (ref "U2") (pin "A26") (pinfunction "GPIO03_PERADDR04_DMAREQ3_A26") (pintype "bidirectional+no_connect"))
    )
    (net (code "105") (name "unconnected-(U2D-GPIO04_PERADDR03_DMAACK3-PadD26)") (class "Default")
      (node (ref "U2") (pin "D26") (pinfunction "GPIO04_PERADDR03_DMAACK3_D26") (pintype "bidirectional+no_connect"))
    )
    (net (code "106") (name "unconnected-(U2D-GPIO05_PERADDR02_EOT3_TC3-PadC26)") (class "Default")
      (node (ref "U2") (pin "C26") (pinfunction "GPIO05_PERADDR02_EOT3_TC3_C26") (pintype "bidirectional+no_connect"))
    )
    (net (code "107") (name "unconnected-(U2D-PERERR_GPIO11-PadC7)") (class "Default")
      (node (ref "U2") (pin "C7") (pinfunction "PERERR_GPIO11_C7") (pintype "bidirectional+no_connect"))
    )
    (net (code "108") (name "unconnected-(U2H-PCIAD00-PadD29)") (class "Default")
      (node (ref "U2") (pin "D29") (pinfunction "PCIAD00_D29") (pintype "bidirectional+no_connect"))
    )
    (net (code "109") (name "unconnected-(U2H-PCIAD01-PadA30)") (class "Default")
      (node (ref "U2") (pin "A30") (pinfunction "PCIAD01_A30") (pintype "bidirectional+no_connect"))
    )
    (net (code "110") (name "unconnected-(U2H-PCIAD02-PadC30)") (class "Default")
      (node (ref "U2") (pin "C30") (pinfunction "PCIAD02_C30") (pintype "bidirectional+no_connect"))
    )
    (net (code "111") (name "unconnected-(U2H-PCIAD03-PadA31)") (class "Default")
      (node (ref "U2") (pin "A31") (pinfunction "PCIAD03_A31") (pintype "bidirectional+no_connect"))
    )
    (net (code "112") (name "unconnected-(U2H-PCIAD04-PadD34)") (class "Default")
      (node (ref "U2") (pin "D34") (pinfunction "PCIAD04_D34") (pintype "bidirectional+no_connect"))
    )
    (net (code "113") (name "unconnected-(U2H-PCIAD05-PadF31)") (class "Default")
      (node (ref "U2") (pin "F31") (pinfunction "PCIAD05_F31") (pintype "bidirectional+no_connect"))
    )
    (net (code "114") (name "unconnected-(U2H-PCIAD06-PadE34)") (class "Default")
      (node (ref "U2") (pin "E34") (pinfunction "PCIAD06_E34") (pintype "bidirectional+no_connect"))
    )
    (net (code "115") (name "unconnected-(U2H-PCIAD07-PadF32)") (class "Default")
      (node (ref "U2") (pin "F32") (pinfunction "PCIAD07_F32") (pintype "bidirectional+no_connect"))
    )
    (net (code "116") (name "unconnected-(U2H-PCIAD08-PadF33)") (class "Default")
      (node (ref "U2") (pin "F33") (pinfunction "PCIAD08_F33") (pintype "bidirectional+no_connect"))
    )
    (net (code "117") (name "unconnected-(U2H-PCIAD09-PadF34)") (class "Default")
      (node (ref "U2") (pin "F34") (pinfunction "PCIAD09_F34") (pintype "bidirectional+no_connect"))
    )
    (net (code "118") (name "unconnected-(U2H-PCIAD10-PadG31)") (class "Default")
      (node (ref "U2") (pin "G31") (pinfunction "PCIAD10_G31") (pintype "bidirectional+no_connect"))
    )
    (net (code "119") (name "unconnected-(U2H-PCIAD11-PadG33)") (class "Default")
      (node (ref "U2") (pin "G33") (pinfunction "PCIAD11_G33") (pintype "bidirectional+no_connect"))
    )
    (net (code "120") (name "unconnected-(U2H-PCIAD12-PadG34)") (class "Default")
      (node (ref "U2") (pin "G34") (pinfunction "PCIAD12_G34") (pintype "bidirectional+no_connect"))
    )
    (net (code "121") (name "unconnected-(U2H-PCIAD13-PadH31)") (class "Default")
      (node (ref "U2") (pin "H31") (pinfunction "PCIAD13_H31") (pintype "bidirectional+no_connect"))
    )
    (net (code "122") (name "unconnected-(U2H-PCIAD14-PadH32)") (class "Default")
      (node (ref "U2") (pin "H32") (pinfunction "PCIAD14_H32") (pintype "bidirectional+no_connect"))
    )
    (net (code "123") (name "unconnected-(U2H-PCIAD15-PadH34)") (class "Default")
      (node (ref "U2") (pin "H34") (pinfunction "PCIAD15_H34") (pintype "bidirectional+no_connect"))
    )
    (net (code "124") (name "unconnected-(U2H-PCIAD16-PadL31)") (class "Default")
      (node (ref "U2") (pin "L31") (pinfunction "PCIAD16_L31") (pintype "bidirectional+no_connect"))
    )
    (net (code "125") (name "unconnected-(U2H-PCIAD17-PadL33)") (class "Default")
      (node (ref "U2") (pin "L33") (pinfunction "PCIAD17_L33") (pintype "bidirectional+no_connect"))
    )
    (net (code "126") (name "unconnected-(U2H-PCIAD18-PadM32)") (class "Default")
      (node (ref "U2") (pin "M32") (pinfunction "PCIAD18_M32") (pintype "bidirectional+no_connect"))
    )
    (net (code "127") (name "unconnected-(U2H-PCIAD19-PadM31)") (class "Default")
      (node (ref "U2") (pin "M31") (pinfunction "PCIAD19_M31") (pintype "bidirectional+no_connect"))
    )
    (net (code "128") (name "unconnected-(U2H-PCIAD20-PadM34)") (class "Default")
      (node (ref "U2") (pin "M34") (pinfunction "PCIAD20_M34") (pintype "bidirectional+no_connect"))
    )
    (net (code "129") (name "unconnected-(U2H-PCIAD21-PadN31)") (class "Default")
      (node (ref "U2") (pin "N31") (pinfunction "PCIAD21_N31") (pintype "bidirectional+no_connect"))
    )
    (net (code "130") (name "unconnected-(U2H-PCIAD22-PadN33)") (class "Default")
      (node (ref "U2") (pin "N33") (pinfunction "PCIAD22_N33") (pintype "bidirectional+no_connect"))
    )
    (net (code "131") (name "unconnected-(U2H-PCIAD23-PadN32)") (class "Default")
      (node (ref "U2") (pin "N32") (pinfunction "PCIAD23_N32") (pintype "bidirectional+no_connect"))
    )
    (net (code "132") (name "unconnected-(U2H-PCIAD24-PadP31)") (class "Default")
      (node (ref "U2") (pin "P31") (pinfunction "PCIAD24_P31") (pintype "bidirectional+no_connect"))
    )
    (net (code "133") (name "unconnected-(U2H-PCIAD25-PadP33)") (class "Default")
      (node (ref "U2") (pin "P33") (pinfunction "PCIAD25_P33") (pintype "bidirectional+no_connect"))
    )
    (net (code "134") (name "unconnected-(U2H-PCIAD26-PadP32)") (class "Default")
      (node (ref "U2") (pin "P32") (pinfunction "PCIAD26_P32") (pintype "bidirectional+no_connect"))
    )
    (net (code "135") (name "unconnected-(U2H-PCIAD27-PadP34)") (class "Default")
      (node (ref "U2") (pin "P34") (pinfunction "PCIAD27_P34") (pintype "bidirectional+no_connect"))
    )
    (net (code "136") (name "unconnected-(U2H-PCIAD28-PadR31)") (class "Default")
      (node (ref "U2") (pin "R31") (pinfunction "PCIAD28_R31") (pintype "bidirectional+no_connect"))
    )
    (net (code "137") (name "unconnected-(U2H-PCIAD29-PadR32)") (class "Default")
      (node (ref "U2") (pin "R32") (pinfunction "PCIAD29_R32") (pintype "bidirectional+no_connect"))
    )
    (net (code "138") (name "unconnected-(U2H-PCIAD30-PadR33)") (class "Default")
      (node (ref "U2") (pin "R33") (pinfunction "PCIAD30_R33") (pintype "bidirectional+no_connect"))
    )
    (net (code "139") (name "unconnected-(U2H-PCIAD31-PadR34)") (class "Default")
      (node (ref "U2") (pin "R34") (pinfunction "PCIAD31_R34") (pintype "bidirectional+no_connect"))
    )
    (net (code "140") (name "unconnected-(U2H-PCIC0_BE#0-PadG32)") (class "Default")
      (node (ref "U2") (pin "G32") (pinfunction "PCIC0_BE#0_G32") (pintype "bidirectional+no_connect"))
    )
    (net (code "141") (name "unconnected-(U2H-PCIC0_BE#1-PadJ31)") (class "Default")
      (node (ref "U2") (pin "J31") (pinfunction "PCIC0_BE#1_J31") (pintype "bidirectional+no_connect"))
    )
    (net (code "142") (name "unconnected-(U2H-PCIC0_BE#2-PadL34)") (class "Default")
      (node (ref "U2") (pin "L34") (pinfunction "PCIC0_BE#2_L34") (pintype "bidirectional+no_connect"))
    )
    (net (code "143") (name "unconnected-(U2H-PCIC0_BE#3-PadN34)") (class "Default")
      (node (ref "U2") (pin "N34") (pinfunction "PCIC0_BE#3_N34") (pintype "bidirectional+no_connect"))
    )
    (net (code "144") (name "unconnected-(U2H-PCIDEVSEL#-PadK32)") (class "Default")
      (node (ref "U2") (pin "K32") (pinfunction "PCIDEVSEL#_K32") (pintype "bidirectional+no_connect"))
    )
    (net (code "145") (name "unconnected-(U2H-PCIFRAME#-PadL32)") (class "Default")
      (node (ref "U2") (pin "L32") (pinfunction "PCIFRAME#_L32") (pintype "bidirectional+no_connect"))
    )
    (net (code "146") (name "unconnected-(U2H-PCIGNT#0_REQ#-PadY34)") (class "Default")
      (node (ref "U2") (pin "Y34") (pinfunction "PCIGNT#0_REQ#_Y34") (pintype "input+no_connect"))
    )
    (net (code "147") (name "unconnected-(U2H-PCIGNT#1-PadY33)") (class "Default")
      (node (ref "U2") (pin "Y33") (pinfunction "PCIGNT#1_Y33") (pintype "input+no_connect"))
    )
    (net (code "148") (name "unconnected-(U2H-PCIGNT#2-PadY32)") (class "Default")
      (node (ref "U2") (pin "Y32") (pinfunction "PCIGNT#2_Y32") (pintype "input+no_connect"))
    )
    (net (code "149") (name "unconnected-(U2H-PCIGNT#3-PadY31)") (class "Default")
      (node (ref "U2") (pin "Y31") (pinfunction "PCIGNT#3_Y31") (pintype "input+no_connect"))
    )
    (net (code "150") (name "unconnected-(U2H-PCIGNT#4-PadAA33)") (class "Default")
      (node (ref "U2") (pin "AA33") (pinfunction "PCIGNT#4_AA33") (pintype "input+no_connect"))
    )
    (net (code "151") (name "unconnected-(U2H-PCIGNT#5-PadAA34)") (class "Default")
      (node (ref "U2") (pin "AA34") (pinfunction "PCIGNT#5_AA34") (pintype "input+no_connect"))
    )
    (net (code "152") (name "unconnected-(U2H-PCIIDSEL-PadT31)") (class "Default")
      (node (ref "U2") (pin "T31") (pinfunction "PCIIDSEL_T31") (pintype "output+no_connect"))
    )
    (net (code "153") (name "unconnected-(U2H-PCIINT#-PadAB34)") (class "Default")
      (node (ref "U2") (pin "AB34") (pinfunction "PCIINT#_AB34") (pintype "input+no_connect"))
    )
    (net (code "154") (name "unconnected-(U2H-PCIIRDY#-PadK33)") (class "Default")
      (node (ref "U2") (pin "K33") (pinfunction "PCIIRDY#_K33") (pintype "bidirectional+no_connect"))
    )
    (net (code "155") (name "unconnected-(U2H-PCIPAR-PadJ32)") (class "Default")
      (node (ref "U2") (pin "J32") (pinfunction "PCIPAR_J32") (pintype "bidirectional+no_connect"))
    )
    (net (code "156") (name "unconnected-(U2H-PCIPERR#-PadJ33)") (class "Default")
      (node (ref "U2") (pin "J33") (pinfunction "PCIPERR#_J33") (pintype "bidirectional+no_connect"))
    )
    (net (code "157") (name "unconnected-(U2H-PCIRESET#-PadAA31)") (class "Default")
      (node (ref "U2") (pin "AA31") (pinfunction "PCIRESET#_AA31") (pintype "input+no_connect"))
    )
    (net (code "158") (name "unconnected-(U30-NC0-PadA1)") (class "Default")
      (node (ref "U30") (pin "A1") (pinfunction "NC0_A1") (pintype "tri_state+no_connect"))
    )
    (net (code "159") (name "unconnected-(U30-NC1-PadC1)") (class "Default")
      (node (ref "U30") (pin "C1") (pinfunction "NC1_C1") (pintype "tri_state+no_connect"))
    )
    (net (code "160") (name "unconnected-(U30-NC2-PadD1)") (class "Default")
      (node (ref "U30") (pin "D1") (pinfunction "NC2_D1") (pintype "tri_state+no_connect"))
    )
    (net (code "161") (name "unconnected-(U30-NC3-PadE1)") (class "Default")
      (node (ref "U30") (pin "E1") (pinfunction "NC3_E1") (pintype "tri_state+no_connect"))
    )
    (net (code "162") (name "unconnected-(U30-NC4-PadG1)") (class "Default")
      (node (ref "U30") (pin "G1") (pinfunction "NC4_G1") (pintype "tri_state+no_connect"))
    )
    (net (code "163") (name "unconnected-(U30-NC5-PadH1)") (class "Default")
      (node (ref "U30") (pin "H1") (pinfunction "NC5_H1") (pintype "tri_state+no_connect"))
    )
    (net (code "164") (name "unconnected-(U30-NC6-PadA8)") (class "Default")
      (node (ref "U30") (pin "A8") (pinfunction "NC6_A8") (pintype "tri_state+no_connect"))
    )
    (net (code "165") (name "unconnected-(U30-NC7-PadH8)") (class "Default")
      (node (ref "U30") (pin "H8") (pinfunction "NC7_H8") (pintype "tri_state+no_connect"))
    )
  )
)
